# 02-bluetooth-V2_3.net
KiCad netlist of a schematic drawn in Altium Designer
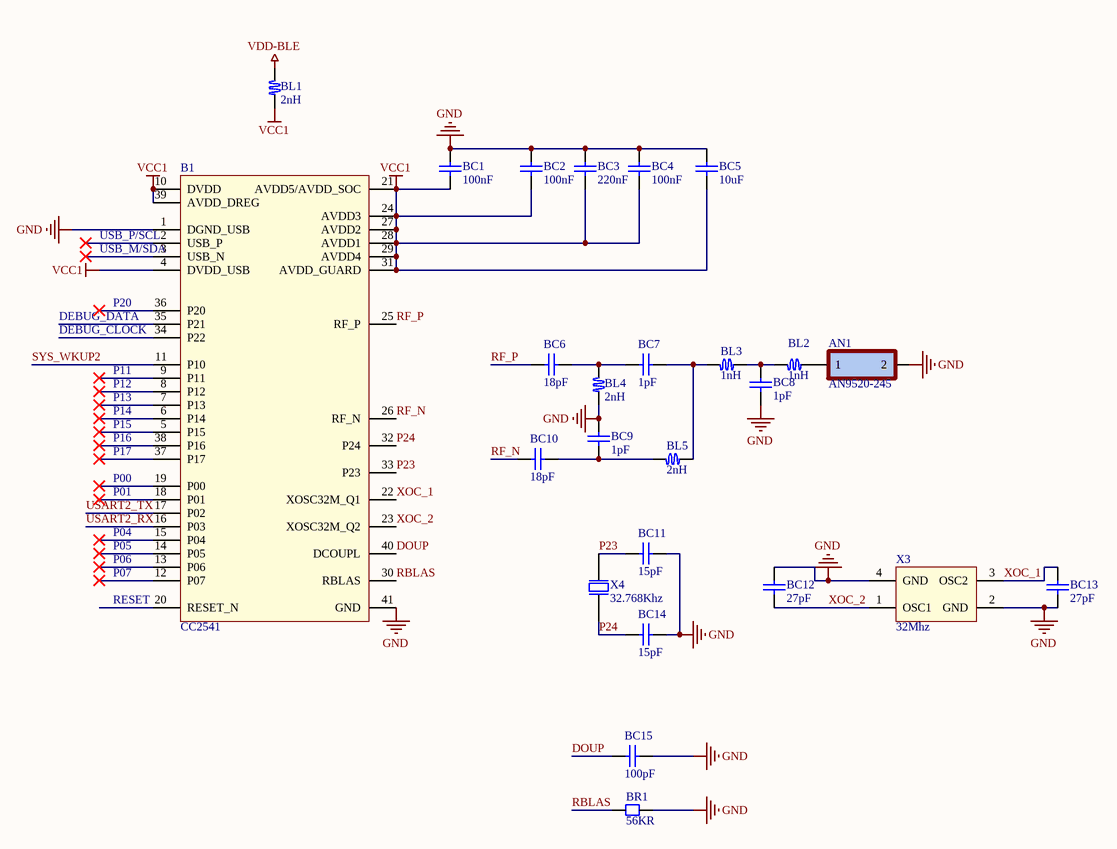
[diagram p0: 02-bluetooth-V2.3.SchDoc]

(export (version "E")
  (design (tool "Eeschema 10.0.6"))
  (components
    (comp (ref "AN1")
      (value "AN9520-245")
      (footprint "AN-5120")
      (description "2.4G全向天线 蓝牙天线 陶瓷贴片 WIFI内置")
      (libsource (lib "tianxiaohua_Schlib") (part "AN9520-245"))
    )
    (comp (ref "B1")
      (value "CC2541")
      (footprint "QFN40-CC254X")
      (description "低功耗蓝牙芯片")
      (libsource (lib "tianxiaohua_Schlib") (part "CC2541"))
    )
    (comp (ref "BC1")
      (value "100nF")
      (footprint "CC1005-0402")
      (description "贴片电容")
      (libsource (lib "tianxiaohua_Schlib") (part "Chip capacitor"))
    )
    (comp (ref "BC2")
      (value "100nF")
      (footprint "CC1005-0402")
      (description "贴片电容")
      (libsource (lib "tianxiaohua_Schlib") (part "Chip capacitor"))
    )
    (comp (ref "BC3")
      (value "220nF")
      (footprint "CC1005-0402")
      (description "贴片电容")
      (libsource (lib "tianxiaohua_Schlib") (part "Chip capacitor"))
    )
    (comp (ref "BC4")
      (value "100nF")
      (footprint "CC1005-0402")
      (description "贴片电容")
      (libsource (lib "tianxiaohua_Schlib") (part "Chip capacitor"))
    )
    (comp (ref "BC5")
      (value "10uF")
      (footprint "CC1005-0402")
      (description "贴片电容")
      (libsource (lib "tianxiaohua_Schlib") (part "Chip capacitor"))
    )
    (comp (ref "BC6")
      (value "18pF")
      (footprint "CC1005-0402")
      (description "贴片电容")
      (libsource (lib "tianxiaohua_Schlib") (part "Chip capacitor"))
    )
    (comp (ref "BC7")
      (value "1pF")
      (footprint "CC1005-0402")
      (description "贴片电容")
      (libsource (lib "tianxiaohua_Schlib") (part "Chip capacitor"))
    )
    (comp (ref "BC8")
      (value "1pF")
      (footprint "CC1005-0402")
      (description "贴片电容")
      (libsource (lib "tianxiaohua_Schlib") (part "Chip capacitor"))
    )
    (comp (ref "BC9")
      (value "1pF")
      (footprint "CC1005-0402")
      (description "贴片电容")
      (libsource (lib "tianxiaohua_Schlib") (part "Chip capacitor"))
    )
    (comp (ref "BC10")
      (value "18pF")
      (footprint "CC1005-0402")
      (description "贴片电容")
      (libsource (lib "tianxiaohua_Schlib") (part "Chip capacitor"))
    )
    (comp (ref "BC11")
      (value "15pF")
      (footprint "CC1005-0402")
      (description "贴片电容")
      (libsource (lib "tianxiaohua_Schlib") (part "Chip capacitor"))
    )
    (comp (ref "BC12")
      (value "27pF")
      (footprint "CC1005-0402")
      (description "贴片电容")
      (libsource (lib "tianxiaohua_Schlib") (part "Chip capacitor"))
    )
    (comp (ref "BC13")
      (value "27pF")
      (footprint "CC1005-0402")
      (description "贴片电容")
      (libsource (lib "tianxiaohua_Schlib") (part "Chip capacitor"))
    )
    (comp (ref "BC14")
      (value "15pF")
      (footprint "CC1005-0402")
      (description "贴片电容")
      (libsource (lib "tianxiaohua_Schlib") (part "Chip capacitor"))
    )
    (comp (ref "BC15")
      (value "100pF")
      (footprint "CC1005-0402")
      (description "贴片电容")
      (libsource (lib "tianxiaohua_Schlib") (part "Chip capacitor"))
    )
    (comp (ref "BL1")
      (value "2nH")
      (footprint "Inductor-0402")
      (description "0402封装的电感")
      (libsource (lib "") (part "Inductor-0402_1"))
    )
    (comp (ref "BL2")
      (value "1nH")
      (footprint "Inductor-0402")
      (description "0402封装的电感")
      (libsource (lib "tianxiaohua_Schlib") (part "Inductor-0402"))
    )
    (comp (ref "BL3")
      (value "1nH")
      (footprint "Inductor-0402")
      (description "0402封装的电感")
      (libsource (lib "tianxiaohua_Schlib") (part "Inductor-0402"))
    )
    (comp (ref "BL4")
      (value "2nH")
      (footprint "Inductor-0402")
      (description "0402封装的电感")
      (libsource (lib "") (part "Inductor-0402_1"))
    )
    (comp (ref "BL5")
      (value "2nH")
      (footprint "Inductor-0402")
      (description "0402封装的电感")
      (libsource (lib "tianxiaohua_Schlib") (part "Inductor-0402"))
    )
    (comp (ref "BR1")
      (value "56KR")
      (footprint "CR1005-0402")
      (description "贴片电阻")
      (libsource (lib "tianxiaohua_Schlib") (part "Chip resistor"))
    )
    (comp (ref "X3")
      (value "32Mhz")
      (footprint "XTAL-2016")
      (description "2016封装的晶振")
      (libsource (lib "tianxiaohua_Schlib") (part "XTAL 2016"))
    )
    (comp (ref "X4")
      (value "32.768Khz")
      (footprint "XTAL-2012")
      (description "2012封装的时钟晶振")
      (libsource (lib "tianxiaohua_Schlib") (part "XTAL 2012"))
    )
  )
  (nets
    (net (code "1") (name "/DEBUG_CLOCK") (class "Default")
      (node (ref "B1") (pin "34") (pinfunction "P22_34") (pintype "passive"))
    )
    (net (code "2") (name "/DEBUG_DATA") (class "Default")
      (node (ref "B1") (pin "35") (pinfunction "P21_35") (pintype "passive"))
    )
    (net (code "3") (name "/DOUP") (class "Default")
      (node (ref "B1") (pin "40") (pinfunction "DCOUPL_40") (pintype "passive"))
      (node (ref "BC15") (pin "2") (pinfunction "2_2") (pintype "passive"))
    )
    (net (code "4") (name "/P00") (class "Default")
      (node (ref "B1") (pin "19") (pinfunction "P00_19") (pintype "passive+no_connect"))
    )
    (net (code "5") (name "/P01") (class "Default")
      (node (ref "B1") (pin "18") (pinfunction "P01_18") (pintype "passive+no_connect"))
    )
    (net (code "6") (name "/P04") (class "Default")
      (node (ref "B1") (pin "15") (pinfunction "P04_15") (pintype "passive+no_connect"))
    )
    (net (code "7") (name "/P05") (class "Default")
      (node (ref "B1") (pin "14") (pinfunction "P05_14") (pintype "passive+no_connect"))
    )
    (net (code "8") (name "/P06") (class "Default")
      (node (ref "B1") (pin "13") (pinfunction "P06_13") (pintype "passive+no_connect"))
    )
    (net (code "9") (name "/P07") (class "Default")
      (node (ref "B1") (pin "12") (pinfunction "P07_12") (pintype "passive+no_connect"))
    )
    (net (code "10") (name "/P11") (class "Default")
      (node (ref "B1") (pin "9") (pinfunction "P11_9") (pintype "passive+no_connect"))
    )
    (net (code "11") (name "/P12") (class "Default")
      (node (ref "B1") (pin "8") (pinfunction "P12_8") (pintype "passive+no_connect"))
    )
    (net (code "12") (name "/P13") (class "Default")
      (node (ref "B1") (pin "7") (pinfunction "P13_7") (pintype "passive+no_connect"))
    )
    (net (code "13") (name "/P14") (class "Default")
      (node (ref "B1") (pin "6") (pinfunction "P14_6") (pintype "passive+no_connect"))
    )
    (net (code "14") (name "/P15") (class "Default")
      (node (ref "B1") (pin "5") (pinfunction "P15_5") (pintype "passive+no_connect"))
    )
    (net (code "15") (name "/P16") (class "Default")
      (node (ref "B1") (pin "38") (pinfunction "P16_38") (pintype "passive+no_connect"))
    )
    (net (code "16") (name "/P17") (class "Default")
      (node (ref "B1") (pin "37") (pinfunction "P17_37") (pintype "passive+no_connect"))
    )
    (net (code "17") (name "/P20") (class "Default")
      (node (ref "B1") (pin "36") (pinfunction "P20_36") (pintype "passive+no_connect"))
    )
    (net (code "18") (name "/P23") (class "Default")
      (node (ref "B1") (pin "33") (pinfunction "P23_33") (pintype "passive"))
      (node (ref "BC11") (pin "1") (pinfunction "1_1") (pintype "passive"))
      (node (ref "X4") (pin "2") (pinfunction "2_2") (pintype "passive"))
    )
    (net (code "19") (name "/P24") (class "Default")
      (node (ref "B1") (pin "32") (pinfunction "P24_32") (pintype "passive"))
      (node (ref "BC14") (pin "1") (pinfunction "1_1") (pintype "passive"))
      (node (ref "X4") (pin "1") (pinfunction "1_1") (pintype "passive"))
    )
    (net (code "20") (name "/RBLAS") (class "Default")
      (node (ref "B1") (pin "30") (pinfunction "RBLAS_30") (pintype "passive"))
      (node (ref "BR1") (pin "1") (pinfunction "1_1") (pintype "passive"))
    )
    (net (code "21") (name "/RESET") (class "Default")
      (node (ref "B1") (pin "20") (pinfunction "RESET_N_20") (pintype "passive"))
    )
    (net (code "22") (name "/RF_N") (class "Default")
      (node (ref "B1") (pin "26") (pinfunction "RF_N_26") (pintype "passive"))
      (node (ref "BC10") (pin "2") (pinfunction "2_2") (pintype "passive"))
    )
    (net (code "23") (name "/RF_P") (class "Default")
      (node (ref "B1") (pin "25") (pinfunction "RF_P_25") (pintype "passive"))
      (node (ref "BC6") (pin "2") (pinfunction "2_2") (pintype "passive"))
    )
    (net (code "24") (name "/SYS_WKUP2") (class "Default")
      (node (ref "B1") (pin "11") (pinfunction "P10_11") (pintype "passive"))
    )
    (net (code "25") (name "/USART2_RX") (class "Default")
      (node (ref "B1") (pin "16") (pinfunction "P03_16") (pintype "passive"))
    )
    (net (code "26") (name "/USART2_TX") (class "Default")
      (node (ref "B1") (pin "17") (pinfunction "P02_17") (pintype "passive"))
    )
    (net (code "27") (name "/USB_M{slash}SDA") (class "Default")
      (node (ref "B1") (pin "3") (pinfunction "USB_N_3") (pintype "passive+no_connect"))
    )
    (net (code "28") (name "/USB_P{slash}SCL") (class "Default")
      (node (ref "B1") (pin "2") (pinfunction "USB_P_2") (pintype "passive+no_connect"))
    )
    (net (code "29") (name "/XOC_1") (class "Default")
      (node (ref "B1") (pin "22") (pinfunction "XOSC32M_Q1_22") (pintype "passive"))
      (node (ref "BC13") (pin "2") (pinfunction "2_2") (pintype "passive"))
      (node (ref "X3") (pin "3") (pinfunction "OSC2_3") (pintype "passive"))
    )
    (net (code "30") (name "/XOC_2") (class "Default")
      (node (ref "B1") (pin "23") (pinfunction "XOSC32M_Q2_23") (pintype "passive"))
      (node (ref "BC12") (pin "1") (pinfunction "1_1") (pintype "passive"))
      (node (ref "X3") (pin "1") (pinfunction "OSC1_1") (pintype "passive"))
    )
    (net (code "31") (name "GND") (class "Default")
      (node (ref "AN1") (pin "2") (pinfunction "2_2") (pintype "passive"))
      (node (ref "B1") (pin "1") (pinfunction "DGND_USB_1") (pintype "passive"))
      (node (ref "B1") (pin "41") (pinfunction "GND_41") (pintype "passive"))
      (node (ref "BC1") (pin "2") (pinfunction "2_2") (pintype "passive"))
      (node (ref "BC11") (pin "2") (pinfunction "2_2") (pintype "passive"))
      (node (ref "BC12") (pin "2") (pinfunction "2_2") (pintype "passive"))
      (node (ref "BC13") (pin "1") (pinfunction "1_1") (pintype "passive"))
      (node (ref "BC14") (pin "2") (pinfunction "2_2") (pintype "passive"))
      (node (ref "BC15") (pin "1") (pinfunction "1_1") (pintype "passive"))
      (node (ref "BC2") (pin "2") (pinfunction "2_2") (pintype "passive"))
      (node (ref "BC3") (pin "2") (pinfunction "2_2") (pintype "passive"))
      (node (ref "BC4") (pin "2") (pinfunction "2_2") (pintype "passive"))
      (node (ref "BC5") (pin "2") (pinfunction "2_2") (pintype "passive"))
      (node (ref "BC8") (pin "1") (pinfunction "1_1") (pintype "passive"))
      (node (ref "BC9") (pin "1") (pinfunction "1_1") (pintype "passive"))
      (node (ref "BL4") (pin "1") (pinfunction "1_1") (pintype "passive"))
      (node (ref "BR1") (pin "2") (pinfunction "2_2") (pintype "passive"))
      (node (ref "X3") (pin "2") (pinfunction "GND_2") (pintype "passive"))
      (node (ref "X3") (pin "4") (pinfunction "GND_4") (pintype "passive"))
    )
    (net (code "32") (name "Net-(AN1-Pad1)") (class "Default")
      (node (ref "AN1") (pin "1") (pinfunction "1_1") (pintype "passive"))
      (node (ref "BL2") (pin "1") (pinfunction "1_1") (pintype "passive"))
    )
    (net (code "33") (name "Net-(BC6-Pad1)") (class "Default")
      (node (ref "BC6") (pin "1") (pinfunction "1_1") (pintype "passive"))
      (node (ref "BC7") (pin "1") (pinfunction "1_1") (pintype "passive"))
      (node (ref "BL4") (pin "2") (pinfunction "2_2") (pintype "passive"))
    )
    (net (code "34") (name "Net-(BC7-Pad2)") (class "Default")
      (node (ref "BC7") (pin "2") (pinfunction "2_2") (pintype "passive"))
      (node (ref "BL3") (pin "2") (pinfunction "2_2") (pintype "passive"))
      (node (ref "BL5") (pin "1") (pinfunction "1_1") (pintype "passive"))
    )
    (net (code "35") (name "Net-(BC8-Pad2)") (class "Default")
      (node (ref "BC8") (pin "2") (pinfunction "2_2") (pintype "passive"))
      (node (ref "BL2") (pin "2") (pinfunction "2_2") (pintype "passive"))
      (node (ref "BL3") (pin "1") (pinfunction "1_1") (pintype "passive"))
    )
    (net (code "36") (name "Net-(BC10-Pad1)") (class "Default")
      (node (ref "BC10") (pin "1") (pinfunction "1_1") (pintype "passive"))
      (node (ref "BC9") (pin "2") (pinfunction "2_2") (pintype "passive"))
      (node (ref "BL5") (pin "2") (pinfunction "2_2") (pintype "passive"))
    )
    (net (code "37") (name "VCC1") (class "Default")
      (node (ref "B1") (pin "10") (pinfunction "DVDD_10") (pintype "passive"))
      (node (ref "B1") (pin "21") (pinfunction "AVDD5/AVDD_SOC_21") (pintype "passive"))
      (node (ref "B1") (pin "24") (pinfunction "AVDD3_24") (pintype "passive"))
      (node (ref "B1") (pin "27") (pinfunction "AVDD2_27") (pintype "passive"))
      (node (ref "B1") (pin "28") (pinfunction "AVDD1_28") (pintype "passive"))
      (node (ref "B1") (pin "29") (pinfunction "AVDD4_29") (pintype "passive"))
      (node (ref "B1") (pin "31") (pinfunction "AVDD_GUARD_31") (pintype "passive"))
      (node (ref "B1") (pin "39") (pinfunction "AVDD_DREG_39") (pintype "passive"))
      (node (ref "B1") (pin "4") (pinfunction "DVDD_USB_4") (pintype "passive"))
      (node (ref "BC1") (pin "1") (pinfunction "1_1") (pintype "passive"))
      (node (ref "BC2") (pin "1") (pinfunction "1_1") (pintype "passive"))
      (node (ref "BC3") (pin "1") (pinfunction "1_1") (pintype "passive"))
      (node (ref "BC4") (pin "1") (pinfunction "1_1") (pintype "passive"))
      (node (ref "BC5") (pin "1") (pinfunction "1_1") (pintype "passive"))
      (node (ref "BL1") (pin "1") (pinfunction "1_1") (pintype "passive"))
    )
    (net (code "38") (name "VDD-BLE") (class "Default")
      (node (ref "BL1") (pin "2") (pinfunction "2_2") (pintype "passive"))
    )
  )
)
